# CONNECTORS.net
KiCad netlist of a schematic drawn in Altium Designer
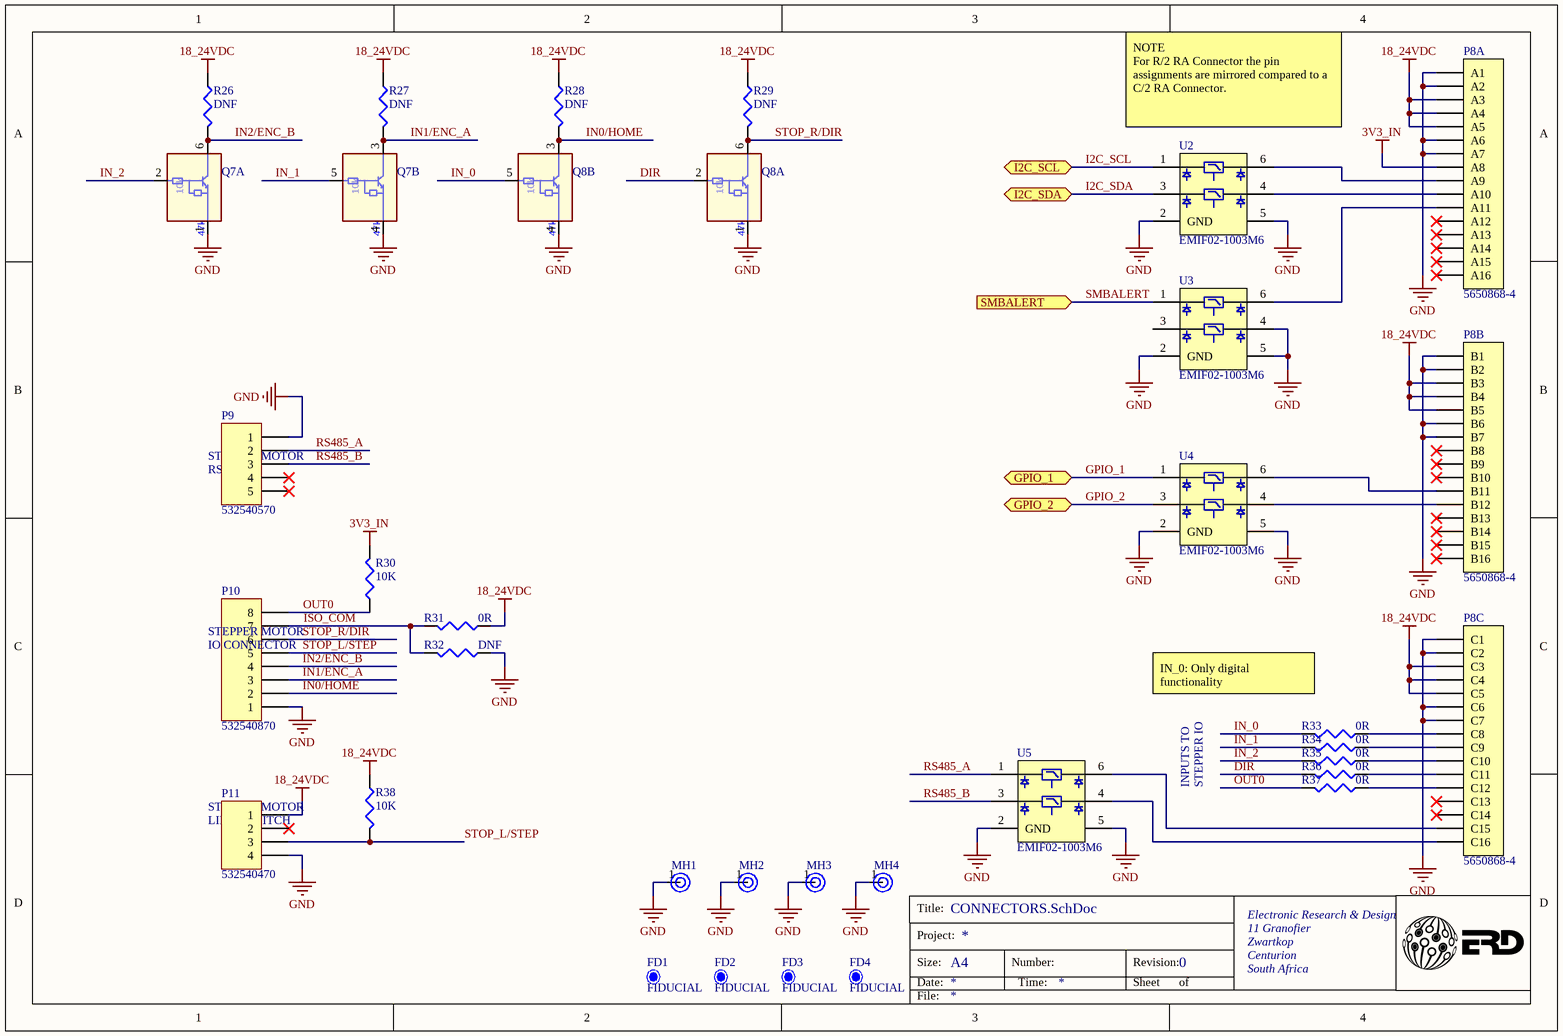
[diagram p0: CONNECTORS.SchDoc]

(export (version "E")
  (design (tool "Eeschema 10.0.6"))
  (components
    (comp (ref "FD1")
      (value "FIDUCIAL")
      (footprint "FIDUCIAL")
      (description "Fiducial 2mm")
      (fields (field (name "PARTNUMBER") "NA"))
      (libsource (lib "*") (part "FIDUCIAL"))
    )
    (comp (ref "FD2")
      (value "FIDUCIAL")
      (footprint "FIDUCIAL")
      (description "Fiducial 2mm")
      (fields (field (name "PARTNUMBER") "NA"))
      (libsource (lib "*") (part "FIDUCIAL"))
    )
    (comp (ref "FD3")
      (value "FIDUCIAL")
      (footprint "FIDUCIAL")
      (description "Fiducial 2mm")
      (fields (field (name "PARTNUMBER") "NA"))
      (libsource (lib "*") (part "FIDUCIAL"))
    )
    (comp (ref "FD4")
      (value "FIDUCIAL")
      (footprint "FIDUCIAL")
      (description "Fiducial 2mm")
      (fields (field (name "PARTNUMBER") "NA"))
      (libsource (lib "*") (part "FIDUCIAL"))
    )
    (comp (ref "MH1")
      (value "MH")
      (footprint "MH - M3")
      (description "Mounting Hole")
      (fields (field (name "PARTNUMBER") "NA"))
      (libsource (lib "BCI_rev_0") (part "MountingHole"))
    )
    (comp (ref "MH2")
      (value "MH")
      (footprint "MH - M3")
      (description "Mounting Hole")
      (fields (field (name "PARTNUMBER") "NA"))
      (libsource (lib "BCI_rev_0") (part "MountingHole"))
    )
    (comp (ref "MH3")
      (value "MH")
      (footprint "MH - M3")
      (description "Mounting Hole")
      (fields (field (name "PARTNUMBER") "NA"))
      (libsource (lib "BCI_rev_0") (part "MountingHole"))
    )
    (comp (ref "MH4")
      (value "MH")
      (footprint "MH - M3")
      (description "Mounting Hole")
      (fields (field (name "PARTNUMBER") "NA"))
      (libsource (lib "BCI_rev_0") (part "MountingHole"))
    )
    (comp (ref "P8")
      (value "5650868-4")
      (footprint "5650868-4_F_RA")
      (description "DIN-41612, R/2, 48-circuit, 3x16, 2.54mm pitch, RA, TH")
      (fields (field (name "MANUFACTURER") "TE Connectivity"))
      (libsource (lib "ERD TiAm") (part "DIN_41612_3x16"))
    )
    (comp (ref "P9")
      (value "532540570")
      (footprint "HDR1X5")
      (description "Header, RA, 5-circuit, 2mm pitch, TH")
      (fields (field (name "MANUFACTURER") "Molex"))
      (libsource (lib "Miscellaneous Connectors") (part "Header 5"))
    )
    (comp (ref "P10")
      (value "532540870")
      (footprint "HDR1X8")
      (description "Header, RA, 8-circuit, 2mm pitch, TH")
      (fields (field (name "MANUFACTURER") "Molex") (field (name "MATING PART") "0510650800"))
      (libsource (lib "Miscellaneous Connectors") (part "Header 8"))
    )
    (comp (ref "P11")
      (value "532540470")
      (footprint "HDR1X4")
      (description "Header, RA, 4-circuit, 2mm pitch, TH")
      (fields (field (name "MANUFACTURER") "Molex"))
      (libsource (lib "Miscellaneous Connectors") (part "Header 4"))
    )
    (comp (ref "Q7")
      (value "DDC114YU-7-F")
      (description "TRANS PREBIASED DUAL NPN SOT363")
      (fields (field (name "MANUFACTURER") "Diodes Inc"))
      (libsource (lib "ERD TiAm") (part "RN1907"))
    )
    (comp (ref "Q8")
      (value "DDC114YU-7-F")
      (description "TRANS PREBIASED DUAL NPN SOT363")
      (fields (field (name "MANUFACTURER") "Diodes Inc"))
      (libsource (lib "ERD TiAm") (part "RN1907"))
    )
    (comp (ref "R26")
      (value "DNF")
      (footprint "RC0402")
      (description "RES, 10K OHM, 1/16W, 1%, 0402")
      (fields (field (name "MANUFACTURER") "Yageo") (field (name "PART NUMBER") "RC0402FR-0710KL"))
      (libsource (lib "ERD TiAm") (part "RES_10K_1/16W_1%_0402"))
    )
    (comp (ref "R27")
      (value "DNF")
      (footprint "RC0402")
      (description "RES, 10K OHM, 1/16W, 1%, 0402")
      (fields (field (name "MANUFACTURER") "Yageo") (field (name "PART NUMBER") "RC0402FR-0710KL"))
      (libsource (lib "ERD TiAm") (part "RES_10K_1/16W_1%_0402"))
    )
    (comp (ref "R28")
      (value "DNF")
      (footprint "RC0402")
      (description "RES, 10K OHM, 1/16W, 1%, 0402")
      (fields (field (name "MANUFACTURER") "Yageo") (field (name "PART NUMBER") "RC0402FR-0710KL"))
      (libsource (lib "ERD TiAm") (part "RES_10K_1/16W_1%_0402"))
    )
    (comp (ref "R29")
      (value "DNF")
      (footprint "RC0402")
      (description "RES, 10K OHM, 1/16W, 1%, 0402")
      (fields (field (name "MANUFACTURER") "Yageo") (field (name "PART NUMBER") "RC0402FR-0710KL"))
      (libsource (lib "ERD TiAm") (part "RES_10K_1/16W_1%_0402"))
    )
    (comp (ref "R30")
      (value "10K")
      (footprint "RC0402")
      (description "RES, 10K OHM, 1/16W, 1%, 0402")
      (fields (field (name "MANUFACTURER") "Yageo") (field (name "PART NUMBER") "RC0402FR-0710KL"))
      (libsource (lib "ERD TiAm") (part "RES_10K_1/16W_1%_0402"))
    )
    (comp (ref "R31")
      (value "0R")
      (footprint "RC0402")
      (description "RES, 0 OHM, 1/16W, 1%, 0402")
      (fields (field (name "MANUFACTURER") "Yageo") (field (name "PARTNUMBER") "RC0402FR-070RL"))
      (libsource (lib "ERD TiAm") (part "RES_10K_1/16W_1%_0402"))
    )
    (comp (ref "R32")
      (value "DNF")
      (footprint "RC0402")
      (description "RES, 0 OHM, 1/16W, 1%, 0402")
      (fields (field (name "MANUFACTURER") "Yageo") (field (name "PARTNUMBER") "RC0402FR-070RL"))
      (libsource (lib "ERD TiAm") (part "RES_10K_1/16W_1%_0402"))
    )
    (comp (ref "R33")
      (value "0R")
      (footprint "RC0402")
      (description "RES, 0 OHM, 1/16W, 1%, 0402")
      (fields (field (name "MANUFACTURER") "Yageo") (field (name "PARTNUMBER") "RC0402FR-070RL"))
      (libsource (lib "ERD TiAm") (part "RES_10K_1/16W_1%_0402"))
    )
    (comp (ref "R34")
      (value "0R")
      (footprint "RC0402")
      (description "RES, 0 OHM, 1/16W, 1%, 0402")
      (fields (field (name "MANUFACTURER") "Yageo") (field (name "PARTNUMBER") "RC0402FR-070RL"))
      (libsource (lib "ERD TiAm") (part "RES_10K_1/16W_1%_0402"))
    )
    (comp (ref "R35")
      (value "0R")
      (footprint "RC0402")
      (description "RES, 0 OHM, 1/16W, 1%, 0402")
      (fields (field (name "MANUFACTURER") "Yageo") (field (name "PARTNUMBER") "RC0402FR-070RL"))
      (libsource (lib "ERD TiAm") (part "RES_10K_1/16W_1%_0402"))
    )
    (comp (ref "R36")
      (value "0R")
      (footprint "RC0402")
      (description "RES, 0 OHM, 1/16W, 1%, 0402")
      (fields (field (name "MANUFACTURER") "Yageo") (field (name "PARTNUMBER") "RC0402FR-070RL"))
      (libsource (lib "ERD TiAm") (part "RES_10K_1/16W_1%_0402"))
    )
    (comp (ref "R37")
      (value "0R")
      (footprint "RC0402")
      (description "RES, 0 OHM, 1/16W, 1%, 0402")
      (fields (field (name "MANUFACTURER") "Yageo") (field (name "PARTNUMBER") "RC0402FR-070RL"))
      (libsource (lib "ERD TiAm") (part "RES_10K_1/16W_1%_0402"))
    )
    (comp (ref "R38")
      (value "10K")
      (footprint "RC0402")
      (description "RES, 10K OHM, 1/16W, 1%, 0402")
      (fields (field (name "MANUFACTURER") "Yageo") (field (name "PART NUMBER") "RC0402FR-0710KL"))
      (libsource (lib "ERD TiAm") (part "RES_10K_1/16W_1%_0402"))
    )
    (comp (ref "U2")
      (value "EMIF02-1003M6")
      (footprint "uQFN-6L")
      (description "EMI Filter, ESD, uQFN-6")
      (libsource (lib "ERD TiAm") (part "EMIF02-1003M6"))
    )
    (comp (ref "U3")
      (value "EMIF02-1003M6")
      (footprint "uQFN-6L")
      (description "EMI Filter, ESD, uQFN-6")
      (libsource (lib "ERD TiAm") (part "EMIF02-1003M6"))
    )
    (comp (ref "U4")
      (value "EMIF02-1003M6")
      (footprint "uQFN-6L")
      (description "EMI Filter, ESD, uQFN-6")
      (libsource (lib "ERD TiAm") (part "EMIF02-1003M6"))
    )
    (comp (ref "U5")
      (value "EMIF02-1003M6")
      (footprint "uQFN-6L")
      (description "EMI Filter, ESD, uQFN-6")
      (libsource (lib "ERD TiAm") (part "EMIF02-1003M6"))
    )
  )
  (nets
    (net (code "1") (name "/DIR") (class "Default")
      (node (ref "Q8") (pin "2") (pinfunction "5_2") (pintype "passive"))
      (node (ref "R36") (pin "2") (pinfunction "2_2") (pintype "passive"))
    )
    (net (code "2") (name "/GPIO_1") (class "Default")
      (node (ref "U4") (pin "1") (pinfunction "1_1") (pintype "passive"))
    )
    (net (code "3") (name "/GPIO_2") (class "Default")
      (node (ref "U4") (pin "3") (pinfunction "3_3") (pintype "passive"))
    )
    (net (code "4") (name "/I2C_SCL") (class "Default")
      (node (ref "U2") (pin "1") (pinfunction "1_1") (pintype "passive"))
    )
    (net (code "5") (name "/I2C_SDA") (class "Default")
      (node (ref "U2") (pin "3") (pinfunction "3_3") (pintype "passive"))
    )
    (net (code "6") (name "/IN0{slash}HOME") (class "Default")
      (node (ref "P10") (pin "2") (pinfunction "2_2") (pintype "passive"))
      (node (ref "Q8") (pin "3") (pinfunction "3_3") (pintype "passive"))
      (node (ref "R28") (pin "1") (pinfunction "1_1") (pintype "passive"))
    )
    (net (code "7") (name "/IN1{slash}ENC_A") (class "Default")
      (node (ref "P10") (pin "3") (pinfunction "3_3") (pintype "passive"))
      (node (ref "Q7") (pin "3") (pinfunction "3_3") (pintype "passive"))
      (node (ref "R27") (pin "1") (pinfunction "1_1") (pintype "passive"))
    )
    (net (code "8") (name "/IN2{slash}ENC_B") (class "Default")
      (node (ref "P10") (pin "4") (pinfunction "4_4") (pintype "passive"))
      (node (ref "Q7") (pin "6") (pinfunction "3_6") (pintype "passive"))
      (node (ref "R26") (pin "1") (pinfunction "1_1") (pintype "passive"))
    )
    (net (code "9") (name "/IN_0") (class "Default")
      (node (ref "Q8") (pin "5") (pinfunction "5_5") (pintype "passive"))
      (node (ref "R33") (pin "2") (pinfunction "2_2") (pintype "passive"))
    )
    (net (code "10") (name "/IN_1") (class "Default")
      (node (ref "Q7") (pin "5") (pinfunction "5_5") (pintype "passive"))
      (node (ref "R34") (pin "2") (pinfunction "2_2") (pintype "passive"))
    )
    (net (code "11") (name "/IN_2") (class "Default")
      (node (ref "Q7") (pin "2") (pinfunction "5_2") (pintype "passive"))
      (node (ref "R35") (pin "2") (pinfunction "2_2") (pintype "passive"))
    )
    (net (code "12") (name "/ISO_COM") (class "Default")
      (node (ref "P10") (pin "7") (pinfunction "7_7") (pintype "passive"))
      (node (ref "R31") (pin "1") (pinfunction "1_1") (pintype "passive"))
      (node (ref "R32") (pin "1") (pinfunction "1_1") (pintype "passive"))
    )
    (net (code "13") (name "/OUT0") (class "Default")
      (node (ref "P10") (pin "8") (pinfunction "8_8") (pintype "passive"))
      (node (ref "R30") (pin "1") (pinfunction "1_1") (pintype "passive"))
      (node (ref "R37") (pin "2") (pinfunction "2_2") (pintype "passive"))
    )
    (net (code "14") (name "/RS485_A") (class "Default")
      (node (ref "P9") (pin "2") (pinfunction "2_2") (pintype "passive"))
      (node (ref "U5") (pin "1") (pinfunction "1_1") (pintype "passive"))
    )
    (net (code "15") (name "/RS485_B") (class "Default")
      (node (ref "P9") (pin "3") (pinfunction "3_3") (pintype "passive"))
      (node (ref "U5") (pin "3") (pinfunction "3_3") (pintype "passive"))
    )
    (net (code "16") (name "/SMBALERT") (class "Default")
      (node (ref "U3") (pin "1") (pinfunction "1_1") (pintype "passive"))
    )
    (net (code "17") (name "/STOP_L{slash}STEP") (class "Default")
      (node (ref "P10") (pin "5") (pinfunction "5_5") (pintype "passive"))
      (node (ref "P11") (pin "3") (pinfunction "3_3") (pintype "passive"))
      (node (ref "R38") (pin "1") (pinfunction "1_1") (pintype "passive"))
    )
    (net (code "18") (name "/STOP_R{slash}DIR") (class "Default")
      (node (ref "P10") (pin "6") (pinfunction "6_6") (pintype "passive"))
      (node (ref "Q8") (pin "6") (pinfunction "3_6") (pintype "passive"))
      (node (ref "R29") (pin "1") (pinfunction "1_1") (pintype "passive"))
    )
    (net (code "19") (name "3V3_IN") (class "Default")
      (node (ref "P8") (pin "8") (pinfunction "A8_8") (pintype "passive"))
      (node (ref "R30") (pin "2") (pinfunction "2_2") (pintype "passive"))
    )
    (net (code "20") (name "18_24VDC") (class "Default")
      (node (ref "P11") (pin "1") (pinfunction "1_1") (pintype "passive"))
      (node (ref "P8") (pin "19") (pinfunction "B3_19") (pintype "passive"))
      (node (ref "P8") (pin "20") (pinfunction "B4_20") (pintype "passive"))
      (node (ref "P8") (pin "21") (pinfunction "B5_21") (pintype "passive"))
      (node (ref "P8") (pin "3") (pinfunction "A3_3") (pintype "passive"))
      (node (ref "P8") (pin "35") (pinfunction "C3_35") (pintype "passive"))
      (node (ref "P8") (pin "36") (pinfunction "C4_36") (pintype "passive"))
      (node (ref "P8") (pin "37") (pinfunction "C5_37") (pintype "passive"))
      (node (ref "P8") (pin "4") (pinfunction "A4_4") (pintype "passive"))
      (node (ref "P8") (pin "5") (pinfunction "A5_5") (pintype "passive"))
      (node (ref "R26") (pin "2") (pinfunction "2_2") (pintype "passive"))
      (node (ref "R27") (pin "2") (pinfunction "2_2") (pintype "passive"))
      (node (ref "R28") (pin "2") (pinfunction "2_2") (pintype "passive"))
      (node (ref "R29") (pin "2") (pinfunction "2_2") (pintype "passive"))
      (node (ref "R31") (pin "2") (pinfunction "2_2") (pintype "passive"))
      (node (ref "R38") (pin "2") (pinfunction "2_2") (pintype "passive"))
    )
    (net (code "21") (name "GND") (class "Default")
      (node (ref "MH1") (pin "1") (pinfunction "1_1") (pintype "passive"))
      (node (ref "MH2") (pin "1") (pinfunction "1_1") (pintype "passive"))
      (node (ref "MH3") (pin "1") (pinfunction "1_1") (pintype "passive"))
      (node (ref "MH4") (pin "1") (pinfunction "1_1") (pintype "passive"))
      (node (ref "P10") (pin "1") (pinfunction "1_1") (pintype "passive"))
      (node (ref "P11") (pin "4") (pinfunction "4_4") (pintype "passive"))
      (node (ref "P8") (pin "1") (pinfunction "A1_1") (pintype "passive"))
      (node (ref "P8") (pin "17") (pinfunction "B1_17") (pintype "passive"))
      (node (ref "P8") (pin "18") (pinfunction "B2_18") (pintype "passive"))
      (node (ref "P8") (pin "2") (pinfunction "A2_2") (pintype "passive"))
      (node (ref "P8") (pin "22") (pinfunction "B6_22") (pintype "passive"))
      (node (ref "P8") (pin "23") (pinfunction "B7_23") (pintype "passive"))
      (node (ref "P8") (pin "33") (pinfunction "C1_33") (pintype "passive"))
      (node (ref "P8") (pin "34") (pinfunction "C2_34") (pintype "passive"))
      (node (ref "P8") (pin "38") (pinfunction "C6_38") (pintype "passive"))
      (node (ref "P8") (pin "39") (pinfunction "C7_39") (pintype "passive"))
      (node (ref "P8") (pin "6") (pinfunction "A6_6") (pintype "passive"))
      (node (ref "P8") (pin "7") (pinfunction "A7_7") (pintype "passive"))
      (node (ref "P9") (pin "1") (pinfunction "1_1") (pintype "passive"))
      (node (ref "Q7") (pin "1") (pinfunction "4_1") (pintype "passive"))
      (node (ref "Q7") (pin "4") (pinfunction "4_4") (pintype "passive"))
      (node (ref "Q8") (pin "1") (pinfunction "4_1") (pintype "passive"))
      (node (ref "Q8") (pin "4") (pinfunction "4_4") (pintype "passive"))
      (node (ref "R32") (pin "2") (pinfunction "2_2") (pintype "passive"))
      (node (ref "U2") (pin "2") (pinfunction "GND_2") (pintype "passive"))
      (node (ref "U2") (pin "5") (pinfunction "GND_5") (pintype "passive"))
      (node (ref "U3") (pin "2") (pinfunction "GND_2") (pintype "passive"))
      (node (ref "U3") (pin "4") (pinfunction "4_4") (pintype "passive"))
      (node (ref "U3") (pin "5") (pinfunction "GND_5") (pintype "passive"))
      (node (ref "U4") (pin "2") (pinfunction "GND_2") (pintype "passive"))
      (node (ref "U4") (pin "5") (pinfunction "GND_5") (pintype "passive"))
      (node (ref "U5") (pin "2") (pinfunction "GND_2") (pintype "passive"))
      (node (ref "U5") (pin "5") (pinfunction "GND_5") (pintype "passive"))
    )
    (net (code "22") (name "Net-(P8A-A9)") (class "Default")
      (node (ref "P8") (pin "9") (pinfunction "A9_9") (pintype "passive"))
      (node (ref "U2") (pin "6") (pinfunction "6_6") (pintype "passive"))
    )
    (net (code "23") (name "Net-(P8A-A10)") (class "Default")
      (node (ref "P8") (pin "10") (pinfunction "A10_10") (pintype "passive"))
      (node (ref "U2") (pin "4") (pinfunction "4_4") (pintype "passive"))
    )
    (net (code "24") (name "Net-(P8A-A11)") (class "Default")
      (node (ref "P8") (pin "11") (pinfunction "A11_11") (pintype "passive"))
      (node (ref "U3") (pin "6") (pinfunction "6_6") (pintype "passive"))
    )
    (net (code "25") (name "Net-(P8B-B11)") (class "Default")
      (node (ref "P8") (pin "27") (pinfunction "B11_27") (pintype "passive"))
      (node (ref "U4") (pin "6") (pinfunction "6_6") (pintype "passive"))
    )
    (net (code "26") (name "Net-(P8B-B12)") (class "Default")
      (node (ref "P8") (pin "28") (pinfunction "B12_28") (pintype "passive"))
      (node (ref "U4") (pin "4") (pinfunction "4_4") (pintype "passive"))
    )
    (net (code "27") (name "Net-(P8C-C8)") (class "Default")
      (node (ref "P8") (pin "40") (pinfunction "C8_40") (pintype "passive"))
      (node (ref "R33") (pin "1") (pinfunction "1_1") (pintype "passive"))
    )
    (net (code "28") (name "Net-(P8C-C9)") (class "Default")
      (node (ref "P8") (pin "41") (pinfunction "C9_41") (pintype "passive"))
      (node (ref "R34") (pin "1") (pinfunction "1_1") (pintype "passive"))
    )
    (net (code "29") (name "Net-(P8C-C10)") (class "Default")
      (node (ref "P8") (pin "42") (pinfunction "C10_42") (pintype "passive"))
      (node (ref "R35") (pin "1") (pinfunction "1_1") (pintype "passive"))
    )
    (net (code "30") (name "Net-(P8C-C11)") (class "Default")
      (node (ref "P8") (pin "43") (pinfunction "C11_43") (pintype "passive"))
      (node (ref "R36") (pin "1") (pinfunction "1_1") (pintype "passive"))
    )
    (net (code "31") (name "Net-(P8C-C12)") (class "Default")
      (node (ref "P8") (pin "44") (pinfunction "C12_44") (pintype "passive"))
      (node (ref "R37") (pin "1") (pinfunction "1_1") (pintype "passive"))
    )
    (net (code "32") (name "Net-(P8C-C15)") (class "Default")
      (node (ref "P8") (pin "47") (pinfunction "C15_47") (pintype "passive"))
      (node (ref "U5") (pin "6") (pinfunction "6_6") (pintype "passive"))
    )
    (net (code "33") (name "Net-(P8C-C16)") (class "Default")
      (node (ref "P8") (pin "48") (pinfunction "C16_48") (pintype "passive"))
      (node (ref "U5") (pin "4") (pinfunction "4_4") (pintype "passive"))
    )
    (net (code "34") (name "unconnected-(P8A-A12-Pad12)") (class "Default")
      (node (ref "P8") (pin "12") (pinfunction "A12_12") (pintype "passive+no_connect"))
    )
    (net (code "35") (name "unconnected-(P8A-A13-Pad13)") (class "Default")
      (node (ref "P8") (pin "13") (pinfunction "A13_13") (pintype "passive+no_connect"))
    )
    (net (code "36") (name "unconnected-(P8A-A14-Pad14)") (class "Default")
      (node (ref "P8") (pin "14") (pinfunction "A14_14") (pintype "passive+no_connect"))
    )
    (net (code "37") (name "unconnected-(P8A-A15-Pad15)") (class "Default")
      (node (ref "P8") (pin "15") (pinfunction "A15_15") (pintype "passive+no_connect"))
    )
    (net (code "38") (name "unconnected-(P8A-A16-Pad16)") (class "Default")
      (node (ref "P8") (pin "16") (pinfunction "A16_16") (pintype "passive+no_connect"))
    )
    (net (code "39") (name "unconnected-(P8B-B8-Pad24)") (class "Default")
      (node (ref "P8") (pin "24") (pinfunction "B8_24") (pintype "passive+no_connect"))
    )
    (net (code "40") (name "unconnected-(P8B-B9-Pad25)") (class "Default")
      (node (ref "P8") (pin "25") (pinfunction "B9_25") (pintype "passive+no_connect"))
    )
    (net (code "41") (name "unconnected-(P8B-B10-Pad26)") (class "Default")
      (node (ref "P8") (pin "26") (pinfunction "B10_26") (pintype "passive+no_connect"))
    )
    (net (code "42") (name "unconnected-(P8B-B13-Pad29)") (class "Default")
      (node (ref "P8") (pin "29") (pinfunction "B13_29") (pintype "passive+no_connect"))
    )
    (net (code "43") (name "unconnected-(P8B-B14-Pad30)") (class "Default")
      (node (ref "P8") (pin "30") (pinfunction "B14_30") (pintype "passive+no_connect"))
    )
    (net (code "44") (name "unconnected-(P8B-B15-Pad31)") (class "Default")
      (node (ref "P8") (pin "31") (pinfunction "B15_31") (pintype "passive+no_connect"))
    )
    (net (code "45") (name "unconnected-(P8B-B16-Pad32)") (class "Default")
      (node (ref "P8") (pin "32") (pinfunction "B16_32") (pintype "passive+no_connect"))
    )
    (net (code "46") (name "unconnected-(P8C-C13-Pad45)") (class "Default")
      (node (ref "P8") (pin "45") (pinfunction "C13_45") (pintype "passive+no_connect"))
    )
    (net (code "47") (name "unconnected-(P8C-C14-Pad46)") (class "Default")
      (node (ref "P8") (pin "46") (pinfunction "C14_46") (pintype "passive+no_connect"))
    )
    (net (code "48") (name "unconnected-(P9-Pad4)") (class "Default")
      (node (ref "P9") (pin "4") (pinfunction "4_4") (pintype "passive+no_connect"))
    )
    (net (code "49") (name "unconnected-(P9-Pad5)") (class "Default")
      (node (ref "P9") (pin "5") (pinfunction "5_5") (pintype "passive+no_connect"))
    )
    (net (code "50") (name "unconnected-(P11-Pad2)") (class "Default")
      (node (ref "P11") (pin "2") (pinfunction "2_2") (pintype "passive+no_connect"))
    )
    (net (code "51") (name "unconnected-(U3-Pad3)") (class "Default")
      (node (ref "U3") (pin "3") (pinfunction "3_3") (pintype "passive"))
    )
  )
)
